# Connectors.net
KiCad netlist of a schematic drawn in Altium Designer
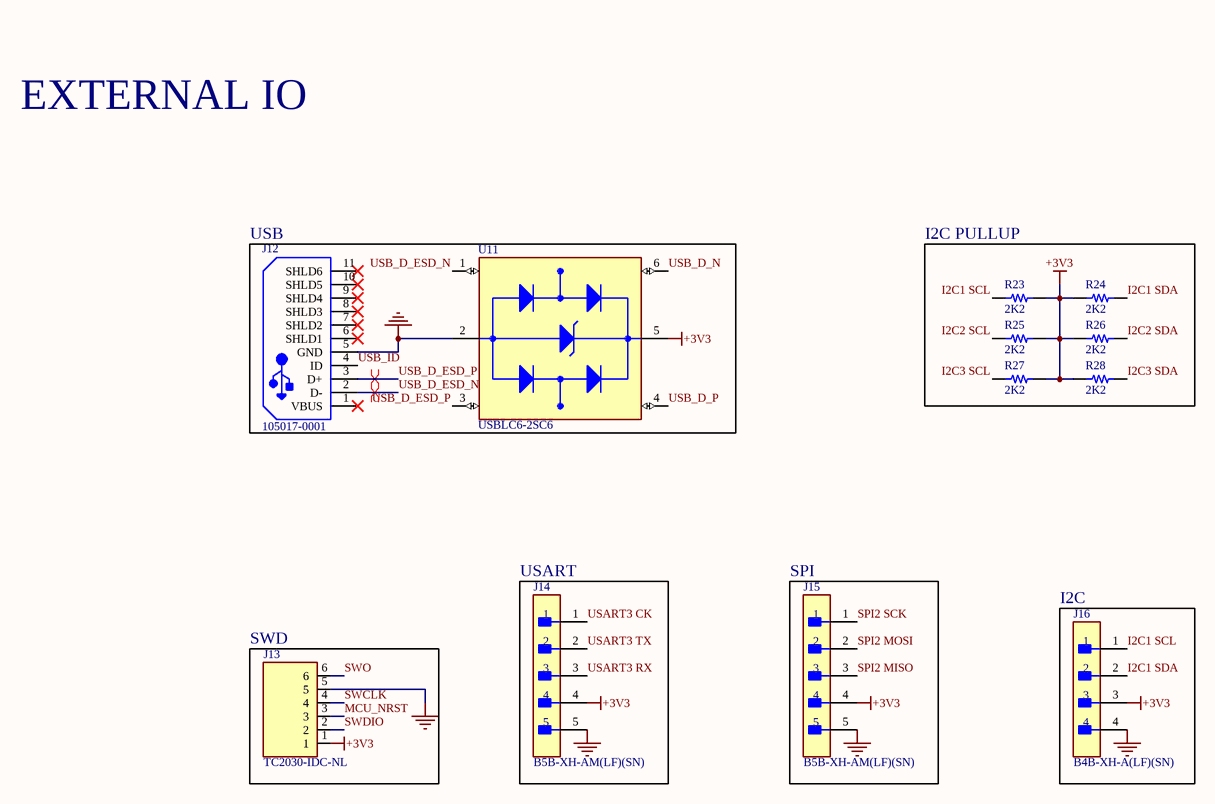
[diagram p0: Connectors.SchDoc]

(export (version "E")
  (design (tool "Eeschema 10.0.6"))
  (components
    (comp (ref "J12")
      (value "105017-0001")
      (footprint "USB-MICRO-B_V")
      (fields (field (name "MANUFACTURER") "Molex"))
      (libsource (lib "Altium Content Vault") (part "USB-5-6SHLD"))
    )
    (comp (ref "J13")
      (value "TC2030-IDC-NL")
      (footprint "TAG_TC2030-IDC-NL")
      (description "CABLE ADAPTER 6 POS")
      (libsource (lib "TC2030-IDC-NL") (part "TC2030-IDC-NL"))
    )
    (comp (ref "J14")
      (value "B5B-XH-AM(LF)(SN)")
      (footprint "FP-B5B-XH-AM_LF_SN-MFG")
      (description "CONN HEADER VERT 5POS 2.5MM")
      (libsource (lib "Altium Content Vault") (part "bf93c07fd2649a848d0ec8585582aab"))
    )
    (comp (ref "J15")
      (value "B5B-XH-AM(LF)(SN)")
      (footprint "FP-B5B-XH-AM_LF_SN-MFG")
      (description "CONN HEADER VERT 5POS 2.5MM")
      (libsource (lib "Altium Content Vault") (part "bf93c07fd2649a848d0ec8585582aab"))
    )
    (comp (ref "J16")
      (value "B4B-XH-A(LF)(SN)")
      (footprint "FP-B4B-XH-A_LF_SN-MFG")
      (description "CONN HEADER VERT 4POS 2.5MM")
      (libsource (lib "Altium Content Vault") (part "299a8cea1bdcbc3624fe62c390fa72c"))
    )
    (comp (ref "R23")
      (value "2K2")
      (footprint "RES 0402_1005")
      (description "0402 JUMPER ON TAPE AND REEL")
      (fields (field (name "PART NUMBER") "5112"))
      (libsource (lib "Celestial Altium Library - altium_library") (part "Resistor"))
    )
    (comp (ref "R24")
      (value "2K2")
      (footprint "RES 0402_1005")
      (description "0402 JUMPER ON TAPE AND REEL")
      (fields (field (name "PART NUMBER") "5112"))
      (libsource (lib "Celestial Altium Library - altium_library") (part "Resistor"))
    )
    (comp (ref "R25")
      (value "2K2")
      (footprint "RES 0402_1005")
      (description "0402 JUMPER ON TAPE AND REEL")
      (fields (field (name "PART NUMBER") "5112"))
      (libsource (lib "Celestial Altium Library - altium_library") (part "Resistor"))
    )
    (comp (ref "R26")
      (value "2K2")
      (footprint "RES 0402_1005")
      (description "0402 JUMPER ON TAPE AND REEL")
      (fields (field (name "PART NUMBER") "5112"))
      (libsource (lib "Celestial Altium Library - altium_library") (part "Resistor"))
    )
    (comp (ref "R27")
      (value "2K2")
      (footprint "RES 0402_1005")
      (description "0402 JUMPER ON TAPE AND REEL")
      (fields (field (name "PART NUMBER") "5112"))
      (libsource (lib "Celestial Altium Library - altium_library") (part "Resistor"))
    )
    (comp (ref "R28")
      (value "2K2")
      (footprint "RES 0402_1005")
      (description "0402 JUMPER ON TAPE AND REEL")
      (fields (field (name "PART NUMBER") "5112"))
      (libsource (lib "Celestial Altium Library - altium_library") (part "Resistor"))
    )
    (comp (ref "U11")
      (value "USBLC6-2SC6")
      (footprint "SOT95P280X145-6N")
      (description "17V Clamp 5A (8/20Âµs) Ipp Tvs Diode Surface Mount SOT-23-6")
      (fields (field (name "MF") "STMicroelectronics"))
      (libsource (lib "USBLC6-2SC6") (part "USBLC6-2SC6"))
    )
  )
  (nets
    (net (code "1") (name "+3V3") (class "Default")
      (node (ref "J13") (pin "1") (pinfunction "1_1") (pintype "passive"))
      (node (ref "J14") (pin "4") (pinfunction "4_4") (pintype "passive"))
      (node (ref "J15") (pin "4") (pinfunction "4_4") (pintype "passive"))
      (node (ref "J16") (pin "3") (pinfunction "3_3") (pintype "passive"))
      (node (ref "R23") (pin "1") (pinfunction "1_1") (pintype "passive"))
      (node (ref "R24") (pin "2") (pinfunction "2_2") (pintype "passive"))
      (node (ref "R25") (pin "1") (pinfunction "1_1") (pintype "passive"))
      (node (ref "R26") (pin "2") (pinfunction "2_2") (pintype "passive"))
      (node (ref "R27") (pin "1") (pinfunction "1_1") (pintype "passive"))
      (node (ref "R28") (pin "2") (pinfunction "2_2") (pintype "passive"))
      (node (ref "U11") (pin "5") (pinfunction "VBUS_5") (pintype "power_in"))
    )
    (net (code "2") (name "/I2C1 SCL") (class "Default")
      (node (ref "J16") (pin "1") (pinfunction "1_1") (pintype "passive"))
      (node (ref "R23") (pin "2") (pinfunction "2_2") (pintype "passive"))
    )
    (net (code "3") (name "/I2C1 SDA") (class "Default")
      (node (ref "J16") (pin "2") (pinfunction "2_2") (pintype "passive"))
      (node (ref "R24") (pin "1") (pinfunction "1_1") (pintype "passive"))
    )
    (net (code "4") (name "/I2C2 SCL") (class "Default")
      (node (ref "R25") (pin "2") (pinfunction "2_2") (pintype "passive"))
    )
    (net (code "5") (name "/I2C2 SDA") (class "Default")
      (node (ref "R26") (pin "1") (pinfunction "1_1") (pintype "passive"))
    )
    (net (code "6") (name "/I2C3 SCL") (class "Default")
      (node (ref "R27") (pin "2") (pinfunction "2_2") (pintype "passive"))
    )
    (net (code "7") (name "/I2C3 SDA") (class "Default")
      (node (ref "R28") (pin "1") (pinfunction "1_1") (pintype "passive"))
    )
    (net (code "8") (name "/MCU_NRST") (class "Default")
      (node (ref "J13") (pin "3") (pinfunction "3_3") (pintype "passive"))
    )
    (net (code "9") (name "/SPI2 MISO") (class "Default")
      (node (ref "J15") (pin "3") (pinfunction "3_3") (pintype "passive"))
    )
    (net (code "10") (name "/SPI2 MOSI") (class "Default")
      (node (ref "J15") (pin "2") (pinfunction "2_2") (pintype "passive"))
    )
    (net (code "11") (name "/SPI2 SCK") (class "Default")
      (node (ref "J15") (pin "1") (pinfunction "1_1") (pintype "passive"))
    )
    (net (code "12") (name "/SWCLK") (class "Default")
      (node (ref "J13") (pin "4") (pinfunction "4_4") (pintype "passive"))
    )
    (net (code "13") (name "/SWDIO") (class "Default")
      (node (ref "J13") (pin "2") (pinfunction "2_2") (pintype "passive"))
    )
    (net (code "14") (name "/SWO") (class "Default")
      (node (ref "J13") (pin "6") (pinfunction "6_6") (pintype "passive"))
    )
    (net (code "15") (name "/USART3 CK") (class "Default")
      (node (ref "J14") (pin "1") (pinfunction "1_1") (pintype "passive"))
    )
    (net (code "16") (name "/USART3 RX") (class "Default")
      (node (ref "J14") (pin "3") (pinfunction "3_3") (pintype "passive"))
    )
    (net (code "17") (name "/USART3 TX") (class "Default")
      (node (ref "J14") (pin "2") (pinfunction "2_2") (pintype "passive"))
    )
    (net (code "18") (name "/USB_D_ESD_N") (class "Default")
      (node (ref "J12") (pin "2") (pinfunction "D-_2") (pintype "passive"))
      (node (ref "U11") (pin "1") (pinfunction "I/O1_IN_1") (pintype "bidirectional"))
    )
    (net (code "19") (name "/USB_D_ESD_P") (class "Default")
      (node (ref "J12") (pin "3") (pinfunction "D+_3") (pintype "passive"))
      (node (ref "U11") (pin "3") (pinfunction "I/O2_IN_3") (pintype "bidirectional"))
    )
    (net (code "20") (name "/USB_D_N") (class "Default")
      (node (ref "U11") (pin "6") (pinfunction "I/O1_OUT_6") (pintype "bidirectional"))
    )
    (net (code "21") (name "/USB_D_P") (class "Default")
      (node (ref "U11") (pin "4") (pinfunction "I/O2_OUT_4") (pintype "bidirectional"))
    )
    (net (code "22") (name "/USB_ID") (class "Default")
      (node (ref "J12") (pin "4") (pinfunction "ID_4") (pintype "passive"))
    )
    (net (code "23") (name "GND") (class "Default")
      (node (ref "J12") (pin "5") (pinfunction "GND_5") (pintype "passive"))
      (node (ref "J13") (pin "5") (pinfunction "5_5") (pintype "passive"))
      (node (ref "J14") (pin "5") (pinfunction "5_5") (pintype "passive"))
      (node (ref "J15") (pin "5") (pinfunction "5_5") (pintype "passive"))
      (node (ref "J16") (pin "4") (pinfunction "4_4") (pintype "passive"))
      (node (ref "U11") (pin "2") (pinfunction "GND_2") (pintype "power_in"))
    )
    (net (code "24") (name "unconnected-(J12-SHLD1-Pad6)") (class "Default")
      (node (ref "J12") (pin "6") (pinfunction "SHLD1_6") (pintype "passive+no_connect"))
    )
    (net (code "25") (name "unconnected-(J12-SHLD2-Pad7)") (class "Default")
      (node (ref "J12") (pin "7") (pinfunction "SHLD2_7") (pintype "passive+no_connect"))
    )
    (net (code "26") (name "unconnected-(J12-SHLD3-Pad8)") (class "Default")
      (node (ref "J12") (pin "8") (pinfunction "SHLD3_8") (pintype "passive+no_connect"))
    )
    (net (code "27") (name "unconnected-(J12-SHLD4-Pad9)") (class "Default")
      (node (ref "J12") (pin "9") (pinfunction "SHLD4_9") (pintype "passive+no_connect"))
    )
    (net (code "28") (name "unconnected-(J12-SHLD5-Pad10)") (class "Default")
      (node (ref "J12") (pin "10") (pinfunction "SHLD5_10") (pintype "passive+no_connect"))
    )
    (net (code "29") (name "unconnected-(J12-SHLD6-Pad11)") (class "Default")
      (node (ref "J12") (pin "11") (pinfunction "SHLD6_11") (pintype "passive+no_connect"))
    )
    (net (code "30") (name "unconnected-(J12-VBUS-Pad1)") (class "Default")
      (node (ref "J12") (pin "1") (pinfunction "VBUS_1") (pintype "passive+no_connect"))
    )
  )
)
